# databank.net
KiCad netlist of a schematic drawn in EAGLE
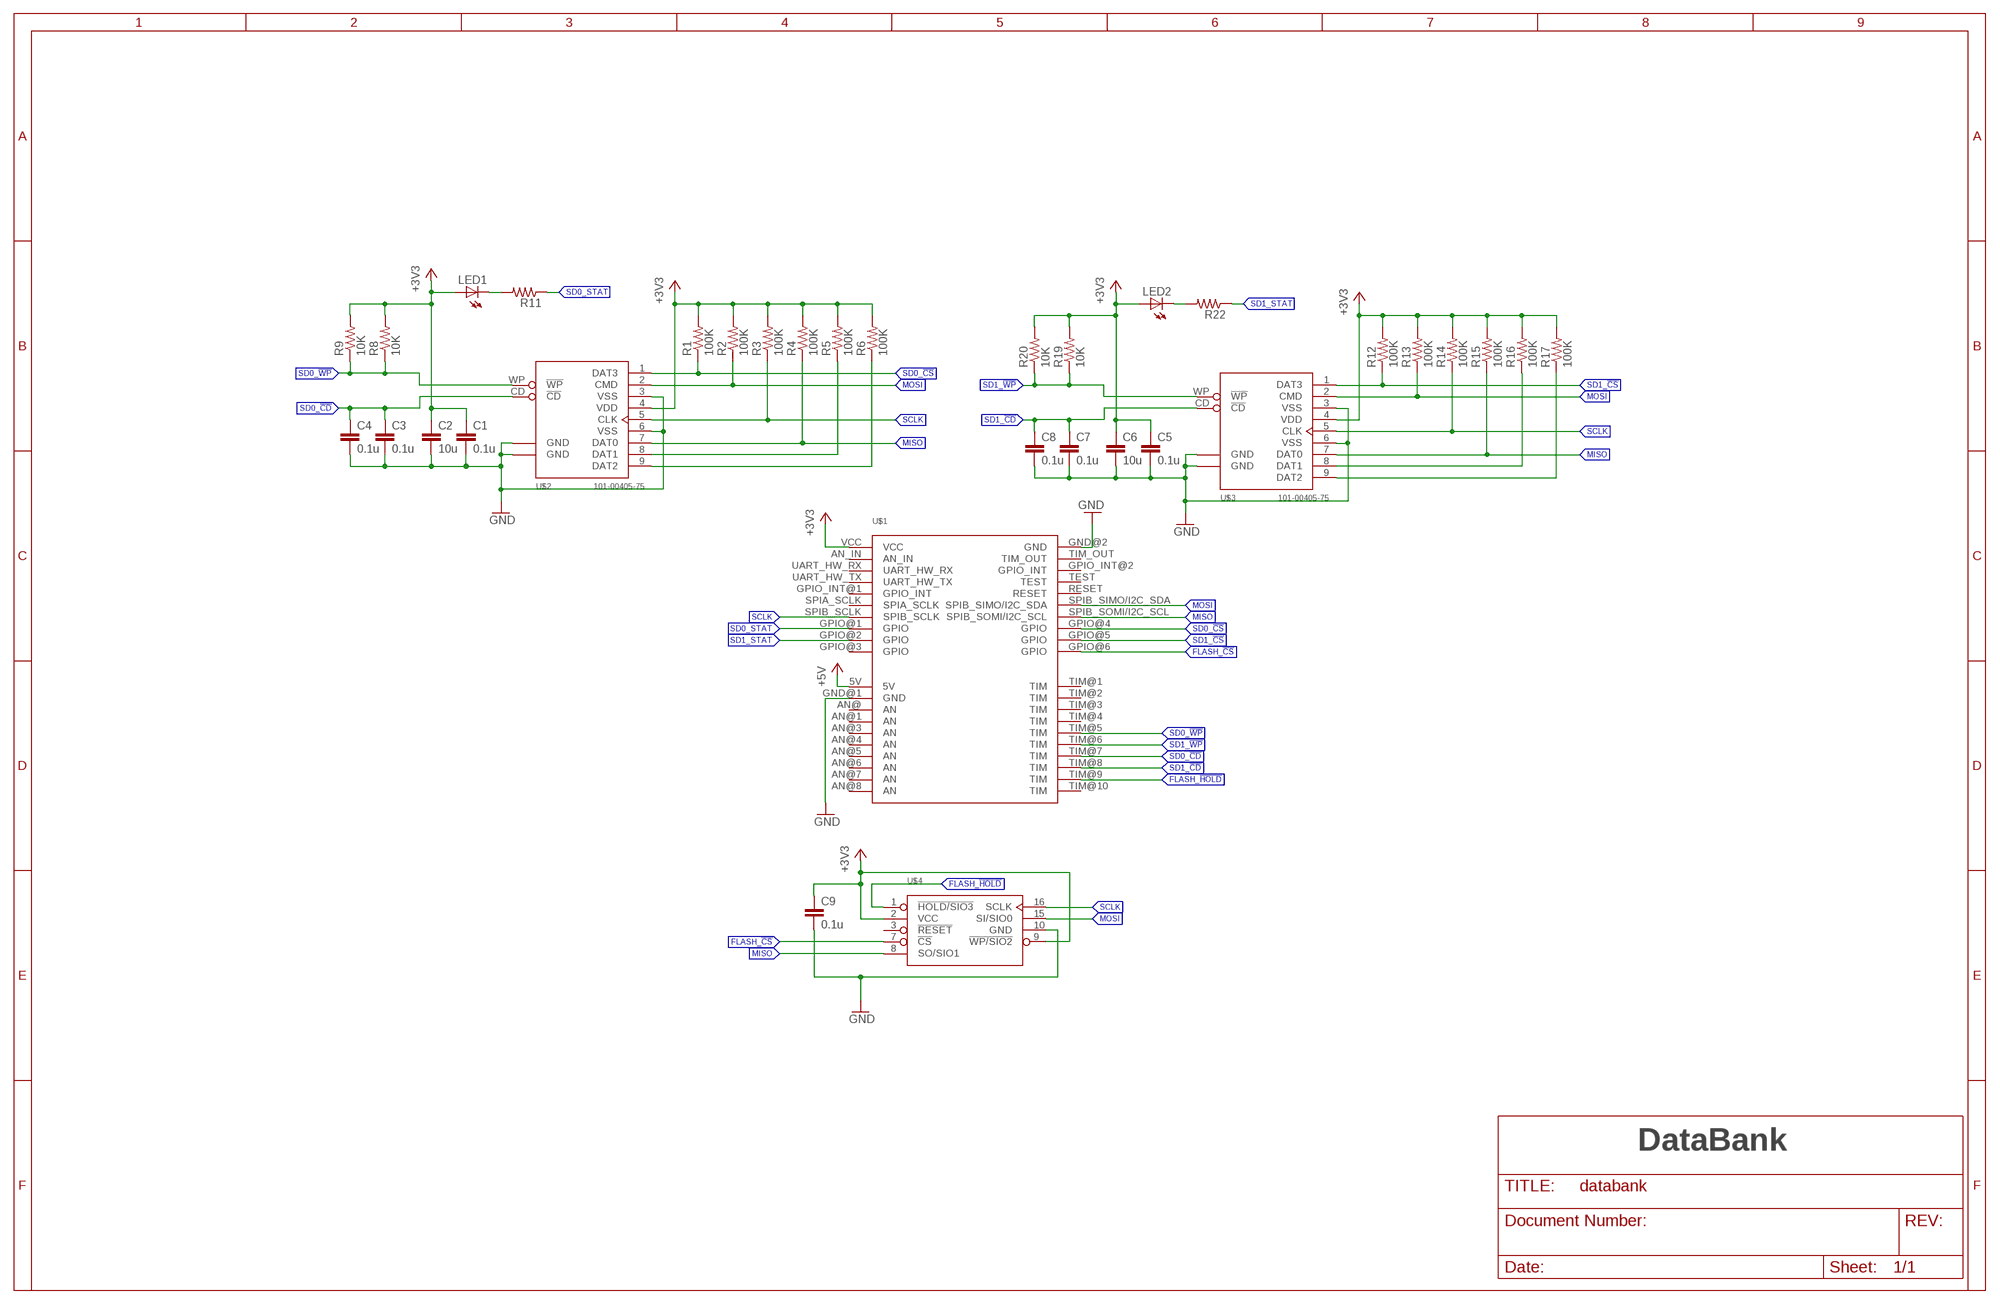
[diagram p0: schematic, sheet 1]

(export (version "E")
  (design (tool "Eeschema 10.0.6"))
  (components
    (comp (ref "C1")
      (value "0.1u")
      (footprint "eagle-import:C0603")
      (libsource (lib "eagle-import") (part "C-EUC0603"))
    )
    (comp (ref "C2")
      (value "10u")
      (footprint "eagle-import:C0603")
      (libsource (lib "eagle-import") (part "C-EUC0603"))
    )
    (comp (ref "C3")
      (value "0.1u")
      (footprint "eagle-import:C0603")
      (libsource (lib "eagle-import") (part "C-EUC0603"))
    )
    (comp (ref "C4")
      (value "0.1u")
      (footprint "eagle-import:C0603")
      (libsource (lib "eagle-import") (part "C-EUC0603"))
    )
    (comp (ref "C5")
      (value "0.1u")
      (footprint "eagle-import:C0603")
      (libsource (lib "eagle-import") (part "C-EUC0603"))
    )
    (comp (ref "C6")
      (value "10u")
      (footprint "eagle-import:C0603")
      (libsource (lib "eagle-import") (part "C-EUC0603"))
    )
    (comp (ref "C7")
      (value "0.1u")
      (footprint "eagle-import:C0603")
      (libsource (lib "eagle-import") (part "C-EUC0603"))
    )
    (comp (ref "C8")
      (value "0.1u")
      (footprint "eagle-import:C0603")
      (libsource (lib "eagle-import") (part "C-EUC0603"))
    )
    (comp (ref "C9")
      (value "0.1u")
      (footprint "eagle-import:C0603")
      (libsource (lib "eagle-import") (part "C-EUC0603"))
    )
    (comp (ref "LED1")
      (value "LEDCHIP-LED0603")
      (footprint "eagle-import:CHIP-LED0603")
      (libsource (lib "eagle-import") (part "LEDCHIP-LED0603"))
    )
    (comp (ref "LED2")
      (value "LEDCHIP-LED0603")
      (footprint "eagle-import:CHIP-LED0603")
      (libsource (lib "eagle-import") (part "LEDCHIP-LED0603"))
    )
    (comp (ref "R1")
      (value "100K")
      (footprint "eagle-import:R0603")
      (libsource (lib "eagle-import") (part "R-US_R0603"))
    )
    (comp (ref "R2")
      (value "100K")
      (footprint "eagle-import:R0603")
      (libsource (lib "eagle-import") (part "R-US_R0603"))
    )
    (comp (ref "R3")
      (value "100K")
      (footprint "eagle-import:R0603")
      (libsource (lib "eagle-import") (part "R-US_R0603"))
    )
    (comp (ref "R4")
      (value "100K")
      (footprint "eagle-import:R0603")
      (libsource (lib "eagle-import") (part "R-US_R0603"))
    )
    (comp (ref "R5")
      (value "100K")
      (footprint "eagle-import:R0603")
      (libsource (lib "eagle-import") (part "R-US_R0603"))
    )
    (comp (ref "R6")
      (value "100K")
      (footprint "eagle-import:R0603")
      (libsource (lib "eagle-import") (part "R-US_R0603"))
    )
    (comp (ref "R8")
      (value "10K")
      (footprint "eagle-import:R0603")
      (libsource (lib "eagle-import") (part "R-US_R0603"))
    )
    (comp (ref "R9")
      (value "10K")
      (footprint "eagle-import:R0603")
      (libsource (lib "eagle-import") (part "R-US_R0603"))
    )
    (comp (ref "R11")
      (value "R-US_R0603")
      (footprint "eagle-import:R0603")
      (libsource (lib "eagle-import") (part "R-US_R0603"))
    )
    (comp (ref "R12")
      (value "100K")
      (footprint "eagle-import:R0603")
      (libsource (lib "eagle-import") (part "R-US_R0603"))
    )
    (comp (ref "R13")
      (value "100K")
      (footprint "eagle-import:R0603")
      (libsource (lib "eagle-import") (part "R-US_R0603"))
    )
    (comp (ref "R14")
      (value "100K")
      (footprint "eagle-import:R0603")
      (libsource (lib "eagle-import") (part "R-US_R0603"))
    )
    (comp (ref "R15")
      (value "100K")
      (footprint "eagle-import:R0603")
      (libsource (lib "eagle-import") (part "R-US_R0603"))
    )
    (comp (ref "R16")
      (value "100K")
      (footprint "eagle-import:R0603")
      (libsource (lib "eagle-import") (part "R-US_R0603"))
    )
    (comp (ref "R17")
      (value "100K")
      (footprint "eagle-import:R0603")
      (libsource (lib "eagle-import") (part "R-US_R0603"))
    )
    (comp (ref "R19")
      (value "10K")
      (footprint "eagle-import:R0603")
      (libsource (lib "eagle-import") (part "R-US_R0603"))
    )
    (comp (ref "R20")
      (value "10K")
      (footprint "eagle-import:R0603")
      (libsource (lib "eagle-import") (part "R-US_R0603"))
    )
    (comp (ref "R22")
      (value "R-US_R0603")
      (footprint "eagle-import:R0603")
      (libsource (lib "eagle-import") (part "R-US_R0603"))
    )
    (comp (ref "U$1")
      (value "LAUNCHPAD_BOOSTER_PACK")
      (footprint "eagle-import:LAUNCHPAD_BOOSTER_PACK")
      (libsource (lib "eagle-import") (part "LAUNCHPAD_BOOSTER_PACK"))
    )
    (comp (ref "U$2")
      (value "101-00405-75")
      (footprint "eagle-import:101-00405-75")
      (libsource (lib "eagle-import") (part "101-00405-75"))
    )
    (comp (ref "U$3")
      (value "101-00405-75")
      (footprint "eagle-import:101-00405-75")
      (libsource (lib "eagle-import") (part "101-00405-75"))
    )
    (comp (ref "U$4")
      (value "MX25L25635E")
      (footprint "eagle-import:SO-16LD")
      (libsource (lib "eagle-import") (part "MX25L25635E"))
    )
  )
  (nets
    (net (code "1") (name "+3V3") (class "Default")
      (node (ref "C1") (pin "1") (pinfunction "1_1") (pintype "passive"))
      (node (ref "C2") (pin "1") (pinfunction "1_1") (pintype "passive"))
      (node (ref "C5") (pin "1") (pinfunction "1_1") (pintype "passive"))
      (node (ref "C6") (pin "1") (pinfunction "1_1") (pintype "passive"))
      (node (ref "C9") (pin "1") (pinfunction "1_1") (pintype "passive"))
      (node (ref "LED1") (pin "A") (pinfunction "A_A") (pintype "passive"))
      (node (ref "LED2") (pin "A") (pinfunction "A_A") (pintype "passive"))
      (node (ref "R1") (pin "2") (pinfunction "2_2") (pintype "passive"))
      (node (ref "R12") (pin "2") (pinfunction "2_2") (pintype "passive"))
      (node (ref "R13") (pin "2") (pinfunction "2_2") (pintype "passive"))
      (node (ref "R14") (pin "2") (pinfunction "2_2") (pintype "passive"))
      (node (ref "R15") (pin "2") (pinfunction "2_2") (pintype "passive"))
      (node (ref "R16") (pin "2") (pinfunction "2_2") (pintype "passive"))
      (node (ref "R17") (pin "2") (pinfunction "2_2") (pintype "passive"))
      (node (ref "R19") (pin "2") (pinfunction "2_2") (pintype "passive"))
      (node (ref "R2") (pin "2") (pinfunction "2_2") (pintype "passive"))
      (node (ref "R20") (pin "2") (pinfunction "2_2") (pintype "passive"))
      (node (ref "R3") (pin "2") (pinfunction "2_2") (pintype "passive"))
      (node (ref "R4") (pin "2") (pinfunction "2_2") (pintype "passive"))
      (node (ref "R5") (pin "2") (pinfunction "2_2") (pintype "passive"))
      (node (ref "R6") (pin "2") (pinfunction "2_2") (pintype "passive"))
      (node (ref "R8") (pin "2") (pinfunction "2_2") (pintype "passive"))
      (node (ref "R9") (pin "2") (pinfunction "2_2") (pintype "passive"))
      (node (ref "U$1") (pin "VCC") (pinfunction "VCC_VCC") (pintype "power_in"))
      (node (ref "U$2") (pin "4") (pinfunction "VDD_4") (pintype "power_in"))
      (node (ref "U$3") (pin "4") (pinfunction "VDD_4") (pintype "power_in"))
      (node (ref "U$4") (pin "2") (pinfunction "VCC_2") (pintype "power_in"))
      (node (ref "U$4") (pin "9") (pinfunction "~{WP/SIO2}_9") (pintype "bidirectional"))
    )
    (net (code "2") (name "+5V") (class "Default")
      (node (ref "U$1") (pin "5V") (pinfunction "5V_5V") (pintype "power_in"))
    )
    (net (code "3") (name "/FLASH_~{CS}") (class "Default")
      (node (ref "U$1") (pin "GPIO@6") (pinfunction "GPIO_GPIO@6") (pintype "bidirectional"))
      (node (ref "U$4") (pin "7") (pinfunction "~{CS}_7") (pintype "input"))
    )
    (net (code "4") (name "/FLASH_~{HOLD}") (class "Default")
      (node (ref "U$1") (pin "TIM@9") (pinfunction "TIM_TIM@9") (pintype "bidirectional"))
      (node (ref "U$4") (pin "1") (pinfunction "~{HOLD/SIO3}_1") (pintype "bidirectional"))
    )
    (net (code "5") (name "/SD0_~{CD}") (class "Default")
      (node (ref "C3") (pin "1") (pinfunction "1_1") (pintype "passive"))
      (node (ref "C4") (pin "1") (pinfunction "1_1") (pintype "passive"))
      (node (ref "U$1") (pin "TIM@7") (pinfunction "TIM_TIM@7") (pintype "bidirectional"))
      (node (ref "U$2") (pin "CD") (pinfunction "~{CD}_CD") (pintype "passive"))
    )
    (net (code "6") (name "/SD0_~{CS}") (class "Default")
      (node (ref "R1") (pin "1") (pinfunction "1_1") (pintype "passive"))
      (node (ref "U$1") (pin "GPIO@4") (pinfunction "GPIO_GPIO@4") (pintype "bidirectional"))
      (node (ref "U$2") (pin "1") (pinfunction "DAT3_1") (pintype "bidirectional"))
    )
    (net (code "7") (name "/SD0_~{WP}") (class "Default")
      (node (ref "R8") (pin "1") (pinfunction "1_1") (pintype "passive"))
      (node (ref "R9") (pin "1") (pinfunction "1_1") (pintype "passive"))
      (node (ref "U$1") (pin "TIM@5") (pinfunction "TIM_TIM@5") (pintype "bidirectional"))
      (node (ref "U$2") (pin "WP") (pinfunction "~{WP}_WP") (pintype "passive"))
    )
    (net (code "8") (name "/SD1_~{CD}") (class "Default")
      (node (ref "C7") (pin "1") (pinfunction "1_1") (pintype "passive"))
      (node (ref "C8") (pin "1") (pinfunction "1_1") (pintype "passive"))
      (node (ref "U$1") (pin "TIM@8") (pinfunction "TIM_TIM@8") (pintype "bidirectional"))
      (node (ref "U$3") (pin "CD") (pinfunction "~{CD}_CD") (pintype "passive"))
    )
    (net (code "9") (name "/SD1_~{CS}") (class "Default")
      (node (ref "R12") (pin "1") (pinfunction "1_1") (pintype "passive"))
      (node (ref "U$1") (pin "GPIO@5") (pinfunction "GPIO_GPIO@5") (pintype "bidirectional"))
      (node (ref "U$3") (pin "1") (pinfunction "DAT3_1") (pintype "bidirectional"))
    )
    (net (code "10") (name "/SD1_~{WP}") (class "Default")
      (node (ref "R19") (pin "1") (pinfunction "1_1") (pintype "passive"))
      (node (ref "R20") (pin "1") (pinfunction "1_1") (pintype "passive"))
      (node (ref "U$1") (pin "TIM@6") (pinfunction "TIM_TIM@6") (pintype "bidirectional"))
      (node (ref "U$3") (pin "WP") (pinfunction "~{WP}_WP") (pintype "passive"))
    )
    (net (code "11") (name "GND") (class "Default")
      (node (ref "C1") (pin "2") (pinfunction "2_2") (pintype "passive"))
      (node (ref "C2") (pin "2") (pinfunction "2_2") (pintype "passive"))
      (node (ref "C3") (pin "2") (pinfunction "2_2") (pintype "passive"))
      (node (ref "C4") (pin "2") (pinfunction "2_2") (pintype "passive"))
      (node (ref "C5") (pin "2") (pinfunction "2_2") (pintype "passive"))
      (node (ref "C6") (pin "2") (pinfunction "2_2") (pintype "passive"))
      (node (ref "C7") (pin "2") (pinfunction "2_2") (pintype "passive"))
      (node (ref "C8") (pin "2") (pinfunction "2_2") (pintype "passive"))
      (node (ref "C9") (pin "2") (pinfunction "2_2") (pintype "passive"))
      (node (ref "U$1") (pin "GND@1") (pinfunction "GND_GND@1") (pintype "power_in"))
      (node (ref "U$1") (pin "GND@2") (pinfunction "GND_GND@2") (pintype "power_in"))
      (node (ref "U$2") (pin "3") (pinfunction "VSS_3") (pintype "power_in"))
      (node (ref "U$2") (pin "6") (pinfunction "VSS_6") (pintype "power_in"))
      (node (ref "U$2") (pin "G1$GND") (pinfunction "GND_G1$GND") (pintype "power_in"))
      (node (ref "U$2") (pin "G2$GND") (pinfunction "GND_G2$GND") (pintype "power_in"))
      (node (ref "U$3") (pin "3") (pinfunction "VSS_3") (pintype "power_in"))
      (node (ref "U$3") (pin "6") (pinfunction "VSS_6") (pintype "power_in"))
      (node (ref "U$3") (pin "G1$GND") (pinfunction "GND_G1$GND") (pintype "power_in"))
      (node (ref "U$3") (pin "G2$GND") (pinfunction "GND_G2$GND") (pintype "power_in"))
      (node (ref "U$4") (pin "10") (pinfunction "GND_10") (pintype "power_in"))
    )
    (net (code "12") (name "MISO") (class "Default")
      (node (ref "R15") (pin "1") (pinfunction "1_1") (pintype "passive"))
      (node (ref "R4") (pin "1") (pinfunction "1_1") (pintype "passive"))
      (node (ref "U$1") (pin "SPIB_SOMI/I2C_SCL") (pinfunction "SPIB_SOMI/I2C_SCL_SPIB_SOMI/I2C_SCL") (pintype "bidirectional"))
      (node (ref "U$2") (pin "7") (pinfunction "DAT0_7") (pintype "bidirectional"))
      (node (ref "U$3") (pin "7") (pinfunction "DAT0_7") (pintype "bidirectional"))
      (node (ref "U$4") (pin "8") (pinfunction "SO/SIO1_8") (pintype "bidirectional"))
    )
    (net (code "13") (name "MOSI") (class "Default")
      (node (ref "R13") (pin "1") (pinfunction "1_1") (pintype "passive"))
      (node (ref "R2") (pin "1") (pinfunction "1_1") (pintype "passive"))
      (node (ref "U$1") (pin "SPIB_SIMO/I2C_SDA") (pinfunction "SPIB_SIMO/I2C_SDA_SPIB_SIMO/I2C_SDA") (pintype "bidirectional"))
      (node (ref "U$2") (pin "2") (pinfunction "CMD_2") (pintype "bidirectional"))
      (node (ref "U$3") (pin "2") (pinfunction "CMD_2") (pintype "bidirectional"))
      (node (ref "U$4") (pin "15") (pinfunction "SI/SIO0_15") (pintype "bidirectional"))
    )
    (net (code "14") (name "Net-(LED1-PadC)") (class "Default")
      (node (ref "LED1") (pin "C") (pinfunction "C_C") (pintype "passive"))
      (node (ref "R11") (pin "2") (pinfunction "2_2") (pintype "passive"))
    )
    (net (code "15") (name "Net-(LED2-PadC)") (class "Default")
      (node (ref "LED2") (pin "C") (pinfunction "C_C") (pintype "passive"))
      (node (ref "R22") (pin "2") (pinfunction "2_2") (pintype "passive"))
    )
    (net (code "16") (name "Net-(U$2-DAT1)") (class "Default")
      (node (ref "R5") (pin "1") (pinfunction "1_1") (pintype "passive"))
      (node (ref "U$2") (pin "8") (pinfunction "DAT1_8") (pintype "bidirectional"))
    )
    (net (code "17") (name "Net-(U$2-DAT2)") (class "Default")
      (node (ref "R6") (pin "1") (pinfunction "1_1") (pintype "passive"))
      (node (ref "U$2") (pin "9") (pinfunction "DAT2_9") (pintype "bidirectional"))
    )
    (net (code "18") (name "Net-(U$3-DAT1)") (class "Default")
      (node (ref "R16") (pin "1") (pinfunction "1_1") (pintype "passive"))
      (node (ref "U$3") (pin "8") (pinfunction "DAT1_8") (pintype "bidirectional"))
    )
    (net (code "19") (name "Net-(U$3-DAT2)") (class "Default")
      (node (ref "R17") (pin "1") (pinfunction "1_1") (pintype "passive"))
      (node (ref "U$3") (pin "9") (pinfunction "DAT2_9") (pintype "bidirectional"))
    )
    (net (code "20") (name "SCLK") (class "Default")
      (node (ref "R14") (pin "1") (pinfunction "1_1") (pintype "passive"))
      (node (ref "R3") (pin "1") (pinfunction "1_1") (pintype "passive"))
      (node (ref "U$1") (pin "SPIB_SCLK") (pinfunction "SPIB_SCLK_SPIB_SCLK") (pintype "bidirectional"))
      (node (ref "U$2") (pin "5") (pinfunction "CLK_5") (pintype "input"))
      (node (ref "U$3") (pin "5") (pinfunction "CLK_5") (pintype "input"))
      (node (ref "U$4") (pin "16") (pinfunction "SCLK_16") (pintype "input"))
    )
    (net (code "21") (name "SD0_STAT") (class "Default")
      (node (ref "R11") (pin "1") (pinfunction "1_1") (pintype "passive"))
      (node (ref "U$1") (pin "GPIO@1") (pinfunction "GPIO_GPIO@1") (pintype "bidirectional"))
    )
    (net (code "22") (name "SD1_STAT") (class "Default")
      (node (ref "R22") (pin "1") (pinfunction "1_1") (pintype "passive"))
      (node (ref "U$1") (pin "GPIO@2") (pinfunction "GPIO_GPIO@2") (pintype "bidirectional"))
    )
    (net (code "23") (name "unconnected-(U$1-AN-PadAN@)") (class "Default")
      (node (ref "U$1") (pin "AN@") (pinfunction "AN_AN@") (pintype "bidirectional"))
    )
    (net (code "24") (name "unconnected-(U$1-AN-PadAN@1)") (class "Default")
      (node (ref "U$1") (pin "AN@1") (pinfunction "AN_AN@1") (pintype "bidirectional"))
    )
    (net (code "25") (name "unconnected-(U$1-AN-PadAN@3)") (class "Default")
      (node (ref "U$1") (pin "AN@3") (pinfunction "AN_AN@3") (pintype "bidirectional"))
    )
    (net (code "26") (name "unconnected-(U$1-AN-PadAN@4)") (class "Default")
      (node (ref "U$1") (pin "AN@4") (pinfunction "AN_AN@4") (pintype "bidirectional"))
    )
    (net (code "27") (name "unconnected-(U$1-AN-PadAN@5)") (class "Default")
      (node (ref "U$1") (pin "AN@5") (pinfunction "AN_AN@5") (pintype "bidirectional"))
    )
    (net (code "28") (name "unconnected-(U$1-AN-PadAN@6)") (class "Default")
      (node (ref "U$1") (pin "AN@6") (pinfunction "AN_AN@6") (pintype "bidirectional"))
    )
    (net (code "29") (name "unconnected-(U$1-AN-PadAN@7)") (class "Default")
      (node (ref "U$1") (pin "AN@7") (pinfunction "AN_AN@7") (pintype "bidirectional"))
    )
    (net (code "30") (name "unconnected-(U$1-AN-PadAN@8)") (class "Default")
      (node (ref "U$1") (pin "AN@8") (pinfunction "AN_AN@8") (pintype "bidirectional"))
    )
    (net (code "31") (name "unconnected-(U$1-GPIO-PadGPIO@3)") (class "Default")
      (node (ref "U$1") (pin "GPIO@3") (pinfunction "GPIO_GPIO@3") (pintype "bidirectional"))
    )
    (net (code "32") (name "unconnected-(U$1-GPIO_INT-PadGPIO_INT@1)") (class "Default")
      (node (ref "U$1") (pin "GPIO_INT@1") (pinfunction "GPIO_INT_GPIO_INT@1") (pintype "bidirectional"))
    )
    (net (code "33") (name "unconnected-(U$1-GPIO_INT-PadGPIO_INT@2)") (class "Default")
      (node (ref "U$1") (pin "GPIO_INT@2") (pinfunction "GPIO_INT_GPIO_INT@2") (pintype "bidirectional"))
    )
    (net (code "34") (name "unconnected-(U$1-PadAN_IN)") (class "Default")
      (node (ref "U$1") (pin "AN_IN") (pinfunction "AN_IN_AN_IN") (pintype "bidirectional"))
    )
    (net (code "35") (name "unconnected-(U$1-PadRESET)") (class "Default")
      (node (ref "U$1") (pin "RESET") (pinfunction "RESET_RESET") (pintype "bidirectional"))
    )
    (net (code "36") (name "unconnected-(U$1-PadSPIA_SCLK)") (class "Default")
      (node (ref "U$1") (pin "SPIA_SCLK") (pinfunction "SPIA_SCLK_SPIA_SCLK") (pintype "bidirectional"))
    )
    (net (code "37") (name "unconnected-(U$1-PadTEST)") (class "Default")
      (node (ref "U$1") (pin "TEST") (pinfunction "TEST_TEST") (pintype "bidirectional"))
    )
    (net (code "38") (name "unconnected-(U$1-PadTIM_OUT)") (class "Default")
      (node (ref "U$1") (pin "TIM_OUT") (pinfunction "TIM_OUT_TIM_OUT") (pintype "bidirectional"))
    )
    (net (code "39") (name "unconnected-(U$1-PadUART_HW_RX)") (class "Default")
      (node (ref "U$1") (pin "UART_HW_RX") (pinfunction "UART_HW_RX_UART_HW_RX") (pintype "bidirectional"))
    )
    (net (code "40") (name "unconnected-(U$1-PadUART_HW_TX)") (class "Default")
      (node (ref "U$1") (pin "UART_HW_TX") (pinfunction "UART_HW_TX_UART_HW_TX") (pintype "bidirectional"))
    )
    (net (code "41") (name "unconnected-(U$1-TIM-PadTIM@1)") (class "Default")
      (node (ref "U$1") (pin "TIM@1") (pinfunction "TIM_TIM@1") (pintype "bidirectional"))
    )
    (net (code "42") (name "unconnected-(U$1-TIM-PadTIM@2)") (class "Default")
      (node (ref "U$1") (pin "TIM@2") (pinfunction "TIM_TIM@2") (pintype "bidirectional"))
    )
    (net (code "43") (name "unconnected-(U$1-TIM-PadTIM@3)") (class "Default")
      (node (ref "U$1") (pin "TIM@3") (pinfunction "TIM_TIM@3") (pintype "bidirectional"))
    )
    (net (code "44") (name "unconnected-(U$1-TIM-PadTIM@4)") (class "Default")
      (node (ref "U$1") (pin "TIM@4") (pinfunction "TIM_TIM@4") (pintype "bidirectional"))
    )
    (net (code "45") (name "unconnected-(U$1-TIM-PadTIM@10)") (class "Default")
      (node (ref "U$1") (pin "TIM@10") (pinfunction "TIM_TIM@10") (pintype "bidirectional"))
    )
    (net (code "46") (name "unconnected-(U$4-~{RESET}-Pad3)") (class "Default")
      (node (ref "U$4") (pin "3") (pinfunction "~{RESET}_3") (pintype "input"))
    )
  )
)
